# LPCB235_-_CAN_Interface.net
KiCad netlist of a schematic drawn in Altium Designer
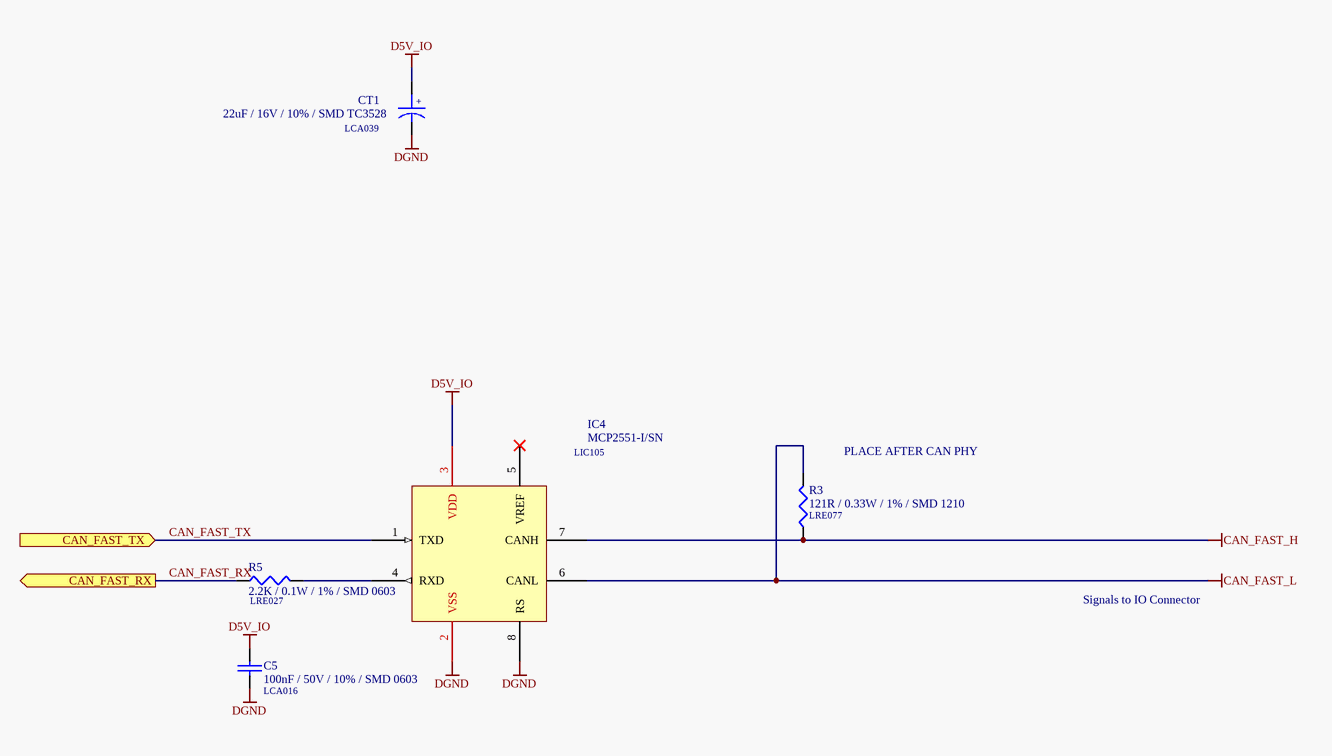
[diagram p0: LPCB235 - CAN Interface.SchDoc]

(export (version "E")
  (design (tool "Eeschema 10.0.6"))
  (components
    (comp (ref "C5")
      (value "100nF / 50V / 10% / SMD 0603")
      (footprint "LFP011__CC1608-0603-IPC7351_B")
      (description "Capacitor, Ceramic Chip, 100nF (0.1uF), 50V, 5%, SMD 0603 [LCA016]")
      (fields (field (name "LDL_NUMBER") "LCA016"))
      (libsource (lib "LDL_Capacitors") (part "100nF / 50V / 10% / SMD 0603"))
    )
    (comp (ref "CT1")
      (value "22uF / 16V / 10% / SMD TC3528")
      (footprint "LFP018__TC3528")
      (description "Capacitor, Tantalum, 22uF, 16V, 10%, SMD TC3528 (BCASE) [LCA039]")
      (fields (field (name "LDL_NUMBER") "LCA039"))
      (libsource (lib "LDL_Capacitors") (part "22uF / 16V / 10% / SMD TC3528"))
    )
    (comp (ref "IC4")
      (value "MCP2551-I/SN")
      (footprint "LFP017__SO-G8/Y1.9")
      (description "IC, High Speed CAN Transceiver, SMD SOIC8 [LIC105]")
      (fields (field (name "LDL_NUMBER") "LIC105"))
      (libsource (lib "LDL_Semiconductors") (part "MCP2551-I/SN"))
    )
    (comp (ref "R3")
      (value "121R / 0.33W / 1% / SMD 1210")
      (footprint "LFP028__CR3225-1210")
      (description "Resistor, Ceramic Chip, 121R, 0.33W, 1%, SMD 1210 [LRE077]")
      (fields (field (name "LDL_NUMBER") "LRE077"))
      (libsource (lib "LDL_Resistors") (part "121R / 0.33W / 1% / SMD 1210"))
    )
    (comp (ref "R5")
      (value "2.2K / 0.1W / 1% / SMD 0603")
      (footprint "LFP020__CR1608-0603-IPC7351_B")
      (description "Resistor, Ceramic Chip, 2.2K, 0.1W, 1%, SMD 0603 [LRE027]")
      (fields (field (name "LDL_NUMBER") "LRE027"))
      (libsource (lib "LDL_Resistors") (part "2.2K / 0.1W / 1% / SMD 0603"))
    )
  )
  (nets
    (net (code "1") (name "/CAN_FAST_RX") (class "Default") (node (ref "R5") (pin "1") (pintype "passive")))
    (net (code "2") (name "/CAN_FAST_TX") (class "Default")
      (node (ref "IC4") (pin "1") (pinfunction "TXD_1") (pintype "input"))
    )
    (net (code "3") (name "CAN_FAST_H") (class "Default")
      (node (ref "IC4") (pin "7") (pinfunction "CANH_7") (pintype "passive"))
      (node (ref "R3") (pin "1") (pintype "passive"))
    )
    (net (code "4") (name "CAN_FAST_L") (class "Default")
      (node (ref "IC4") (pin "6") (pinfunction "CANL_6") (pintype "passive"))
      (node (ref "R3") (pin "2") (pintype "passive"))
    )
    (net (code "5") (name "D5V_IO") (class "Default")
      (node (ref "C5") (pin "1") (pintype "passive"))
      (node (ref "CT1") (pin "1") (pinfunction "1_1") (pintype "passive"))
      (node (ref "IC4") (pin "3") (pinfunction "VDD_3") (pintype "passive"))
    )
    (net (code "6") (name "DGND") (class "Default")
      (node (ref "C5") (pin "2") (pintype "passive"))
      (node (ref "CT1") (pin "2") (pinfunction "2_2") (pintype "passive"))
      (node (ref "IC4") (pin "2") (pinfunction "VSS_2") (pintype "passive"))
      (node (ref "IC4") (pin "8") (pinfunction "RS_8") (pintype "passive"))
    )
    (net (code "7") (name "Net-(IC4-RXD)") (class "Default")
      (node (ref "IC4") (pin "4") (pinfunction "RXD_4") (pintype "output"))
      (node (ref "R5") (pin "2") (pintype "passive"))
    )
    (net (code "8") (name "unconnected-(IC4-VREF-Pad5)") (class "Default")
      (node (ref "IC4") (pin "5") (pinfunction "VREF_5") (pintype "passive+no_connect"))
    )
  )
)
